# MiniSystem_Ports.net
KiCad netlist of a schematic drawn in Altium Designer
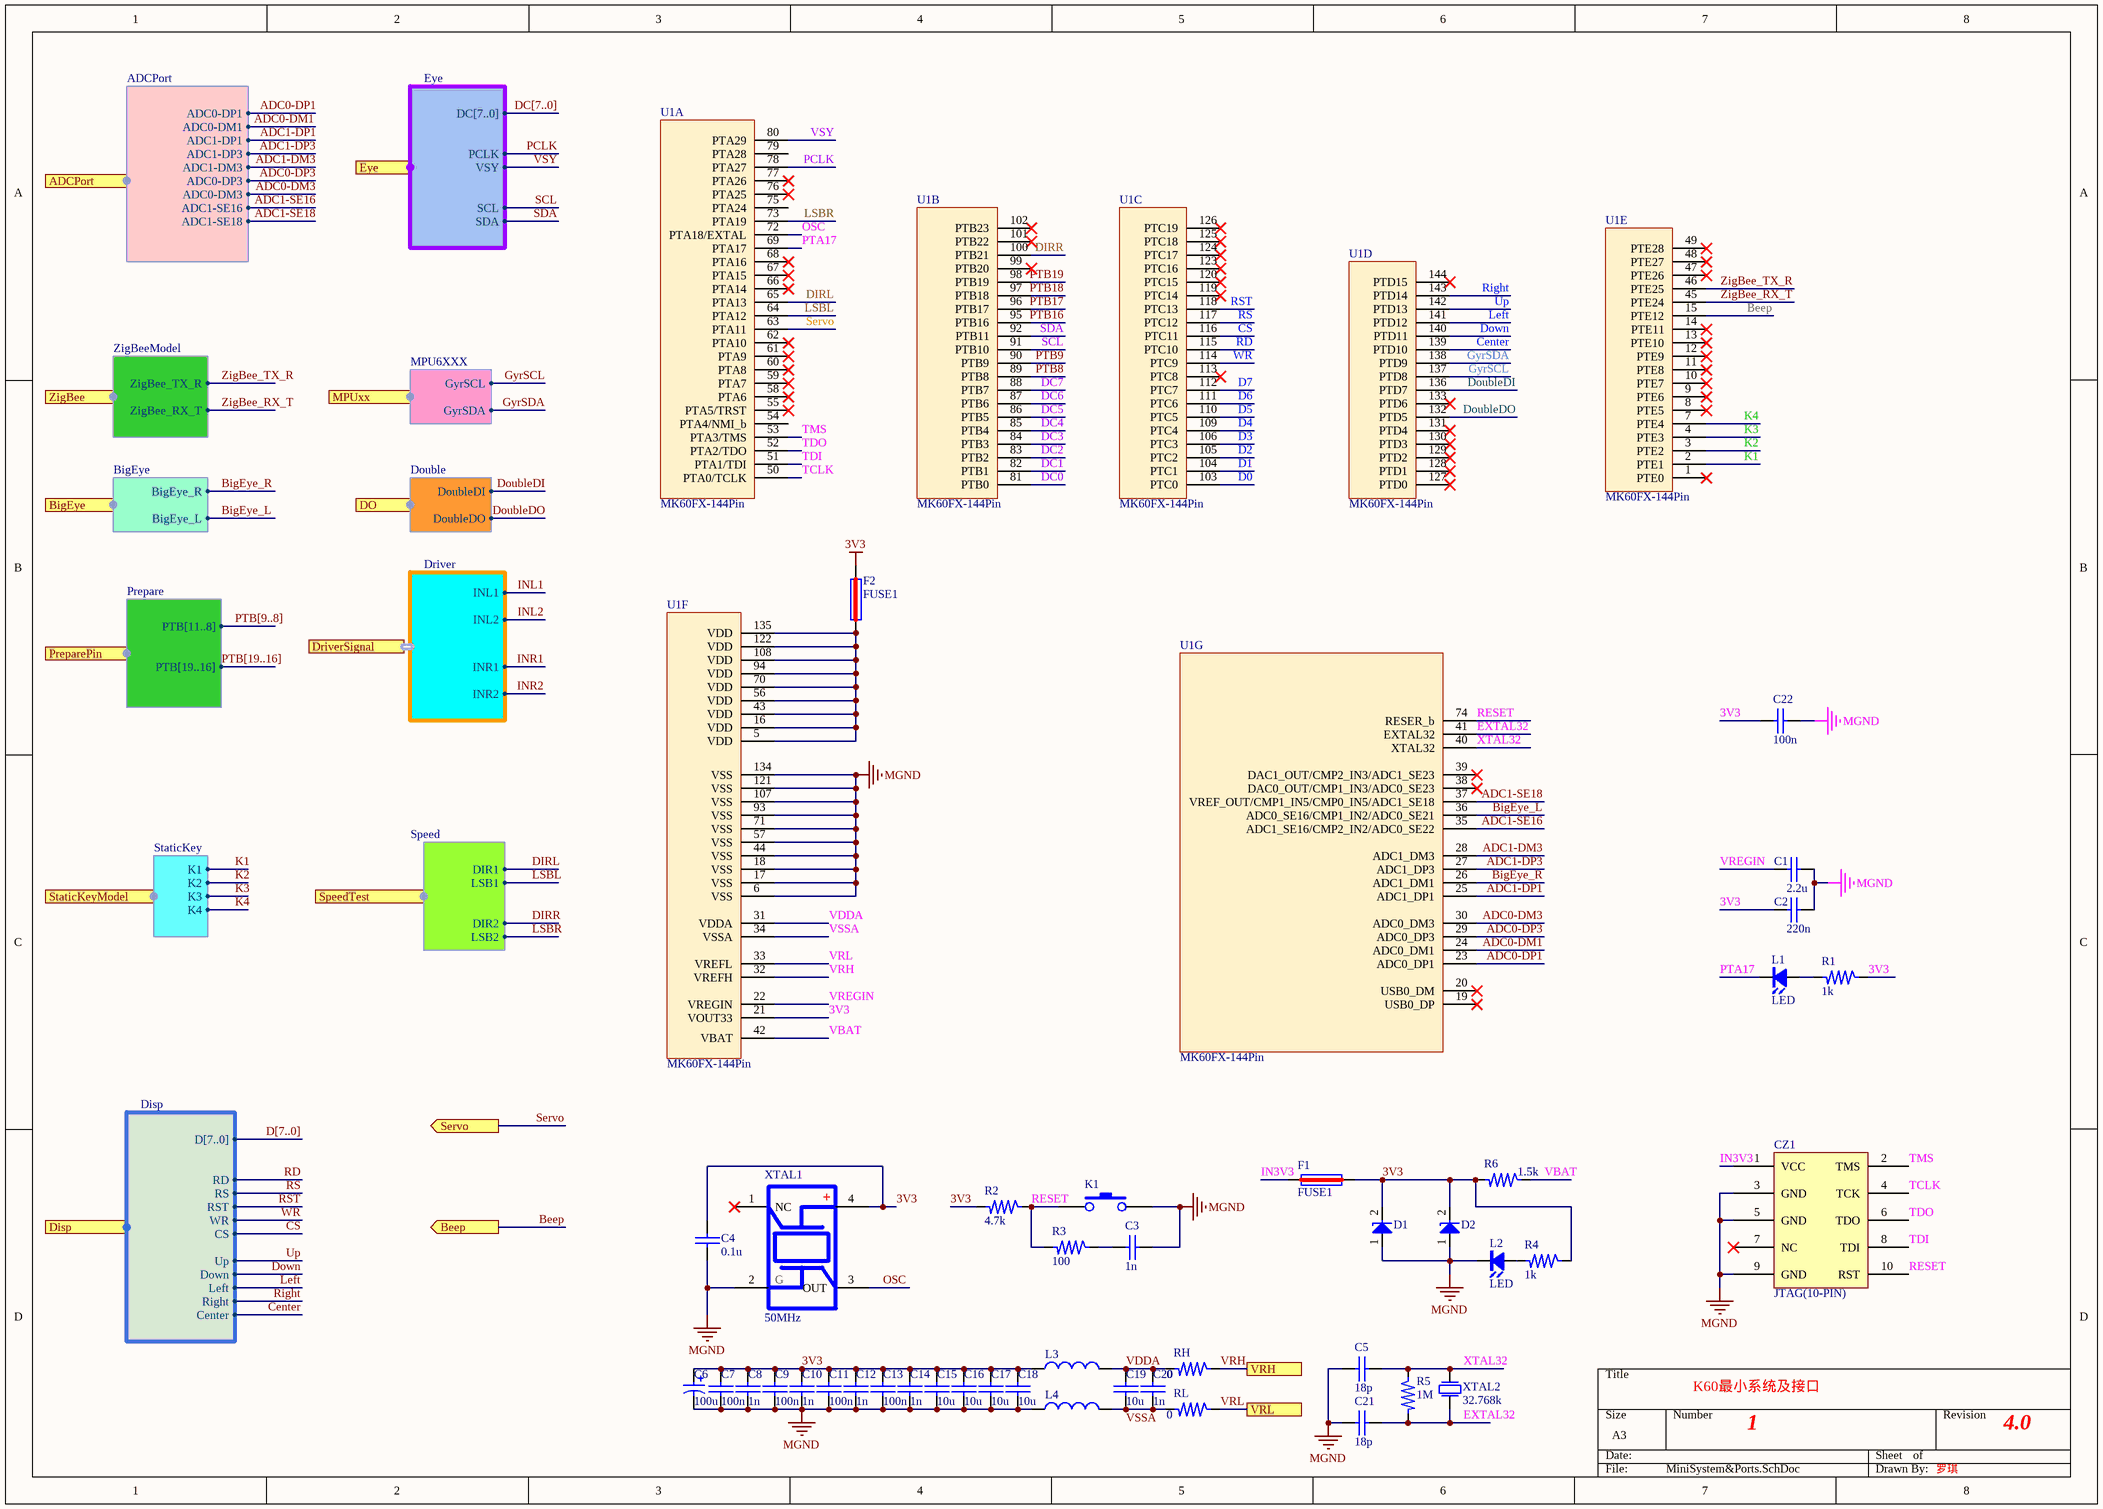
[diagram p0: MiniSystem&Ports.SchDoc]

(export (version "E")
  (design (tool "Eeschema 10.0.6"))
  (components
    (comp (ref "C1")
      (value "2.2u")
      (footprint "C0603")
      (description "电容")
      (libsource (lib "LQ_Integrated_Library") (part "Capacitor"))
    )
    (comp (ref "C2")
      (value "220n")
      (footprint "C0603")
      (description "电容")
      (libsource (lib "LQ_Integrated_Library") (part "Capacitor"))
    )
    (comp (ref "C3")
      (value "1n")
      (footprint "C0603")
      (description "电容")
      (libsource (lib "LQ_Integrated_Library") (part "Capacitor"))
    )
    (comp (ref "C4")
      (value "0.1u")
      (footprint "C0603")
      (description "电容")
      (libsource (lib "LQ_Integrated_Library") (part "Capacitor"))
    )
    (comp (ref "C5")
      (value "18p")
      (footprint "C0603")
      (description "电容")
      (libsource (lib "LQ_Integrated_Library") (part "Capacitor"))
    )
    (comp (ref "C6")
      (value "100u")
      (footprint "CAP-E SMD-C")
      (description "极性电容")
      (libsource (lib "LQ_Integrated_Library") (part "Capacitor-Polarity"))
    )
    (comp (ref "C7")
      (value "100n")
      (footprint "C0603")
      (description "电容")
      (libsource (lib "LQ_Integrated_Library") (part "Capacitor"))
    )
    (comp (ref "C8")
      (value "1n")
      (footprint "C0603")
      (description "电容")
      (libsource (lib "LQ_Integrated_Library") (part "Capacitor"))
    )
    (comp (ref "C9")
      (value "100n")
      (footprint "C0603")
      (description "电容")
      (libsource (lib "LQ_Integrated_Library") (part "Capacitor"))
    )
    (comp (ref "C10")
      (value "1n")
      (footprint "C0603")
      (description "电容")
      (libsource (lib "LQ_Integrated_Library") (part "Capacitor"))
    )
    (comp (ref "C11")
      (value "100n")
      (footprint "C0603")
      (description "电容")
      (libsource (lib "LQ_Integrated_Library") (part "Capacitor"))
    )
    (comp (ref "C12")
      (value "1n")
      (footprint "C0603")
      (description "电容")
      (libsource (lib "LQ_Integrated_Library") (part "Capacitor"))
    )
    (comp (ref "C13")
      (value "100n")
      (footprint "C0603")
      (description "电容")
      (libsource (lib "LQ_Integrated_Library") (part "Capacitor"))
    )
    (comp (ref "C14")
      (value "1n")
      (footprint "C0603")
      (description "电容")
      (libsource (lib "LQ_Integrated_Library") (part "Capacitor"))
    )
    (comp (ref "C15")
      (value "10u")
      (footprint "C0805")
      (description "电容")
      (libsource (lib "LQ_Integrated_Library") (part "Capacitor"))
    )
    (comp (ref "C16")
      (value "10u")
      (footprint "C0805")
      (description "电容")
      (libsource (lib "LQ_Integrated_Library") (part "Capacitor"))
    )
    (comp (ref "C17")
      (value "10u")
      (footprint "C0805")
      (description "电容")
      (libsource (lib "LQ_Integrated_Library") (part "Capacitor"))
    )
    (comp (ref "C18")
      (value "10u")
      (footprint "C0805")
      (description "电容")
      (libsource (lib "LQ_Integrated_Library") (part "Capacitor"))
    )
    (comp (ref "C19")
      (value "10u")
      (footprint "C0805")
      (description "电容")
      (libsource (lib "LQ_Integrated_Library") (part "Capacitor"))
    )
    (comp (ref "C20")
      (value "1n")
      (footprint "C0603")
      (description "电容")
      (libsource (lib "LQ_Integrated_Library") (part "Capacitor"))
    )
    (comp (ref "C21")
      (value "18p")
      (footprint "C0603")
      (description "电容")
      (libsource (lib "LQ_Integrated_Library") (part "Capacitor"))
    )
    (comp (ref "C22")
      (value "100n")
      (footprint "C0603")
      (description "电容")
      (libsource (lib "LQ_Integrated_Library") (part "Capacitor"))
    )
    (comp (ref "CZ1")
      (value "JTAG(10-PIN)")
      (footprint "JTAG 10-pin Header")
      (libsource (lib "LQ_Integrated_Library") (part "JTAG(10-PIN)"))
    )
    (comp (ref "D1")
      (value "EN5819")
      (footprint "D1206")
      (libsource (lib "LQ_Integrated_Library") (part "DIODE稳压"))
    )
    (comp (ref "D2")
      (value "EN5819")
      (footprint "D1206")
      (libsource (lib "LQ_Integrated_Library") (part "DIODE稳压"))
    )
    (comp (ref "F1")
      (value "FUSE1")
      (footprint "FUSE-F1210")
      (description "FUSE")
      (libsource (lib "LQ_Integrated_Library") (part "FUSE1"))
    )
    (comp (ref "F2")
      (value "FUSE1")
      (footprint "FUSE-F1210")
      (description "FUSE")
      (libsource (lib "LQ_Integrated_Library") (part "FUSE1"))
    )
    (comp (ref "K1")
      (value "SW")
      (footprint "KEY-K2")
      (description "按键")
      (libsource (lib "LQ_Integrated_Library") (part "KEY"))
    )
    (comp (ref "L1")
      (value "LED")
      (footprint "LED0805TB")
      (libsource (lib "LQ_Integrated_Library") (part "LED"))
    )
    (comp (ref "L2")
      (value "LED")
      (footprint "LED0805TB")
      (libsource (lib "LQ_Integrated_Library") (part "LED"))
    )
    (comp (ref "L3")
      (value "INDUCTOR")
      (footprint "L0805")
      (description "Inductor")
      (libsource (lib "LQ_Integrated_Library") (part "INDUCTOR"))
    )
    (comp (ref "L4")
      (value "INDUCTOR")
      (footprint "L0805")
      (description "Inductor")
      (libsource (lib "LQ_Integrated_Library") (part "INDUCTOR"))
    )
    (comp (ref "R1")
      (value "1k")
      (footprint "R0603")
      (description "电阻")
      (libsource (lib "LQ_Integrated_Library") (part "Resistor"))
    )
    (comp (ref "R2")
      (value "4.7k")
      (footprint "R0603")
      (description "电阻")
      (libsource (lib "LQ_Integrated_Library") (part "Resistor"))
    )
    (comp (ref "R3")
      (value "100")
      (footprint "R0603")
      (description "电阻")
      (libsource (lib "LQ_Integrated_Library") (part "Resistor"))
    )
    (comp (ref "R4")
      (value "1k")
      (footprint "R0603")
      (description "电阻")
      (libsource (lib "LQ_Integrated_Library") (part "Resistor"))
    )
    (comp (ref "R5")
      (value "1M")
      (footprint "R0603")
      (description "电阻")
      (libsource (lib "LQ_Integrated_Library") (part "Resistor"))
    )
    (comp (ref "R6")
      (value "1.5k")
      (footprint "R0603")
      (description "电阻")
      (libsource (lib "LQ_Integrated_Library") (part "Resistor"))
    )
    (comp (ref "RH")
      (value "0")
      (footprint "R0603")
      (description "电阻")
      (libsource (lib "LQ_Integrated_Library") (part "Resistor"))
    )
    (comp (ref "RL")
      (value "0")
      (footprint "R0603")
      (description "电阻")
      (libsource (lib "LQ_Integrated_Library") (part "Resistor"))
    )
    (comp (ref "U1") (value "MK60FX-144Pin") (footprint "LQFP144") (libsource (lib "") (part "MK60FX144_1")))
    (comp (ref "XTAL1")
      (value "50MHz")
      (footprint "XTAL-6035")
      (libsource (lib "LQ_Integrated_Library") (part "XTAL-Active"))
    )
    (comp (ref "XTAL2")
      (value "32.768k")
      (footprint "XTAL_32.768")
      (description "CRYSTAL")
      (libsource (lib "LQ_Integrated_Library") (part "XTAL"))
    )
  )
  (nets
    (net (code "12") (name "/ADC0-DM1") (class "Default")
      (node (ref "U1") (pin "24") (pinfunction "ADC0_DM1_24") (pintype "passive"))
    )
    (net (code "13") (name "/ADC0-DM3") (class "Default")
      (node (ref "U1") (pin "30") (pinfunction "ADC0_DM3_30") (pintype "passive"))
    )
    (net (code "14") (name "/ADC0-DP1") (class "Default")
      (node (ref "U1") (pin "23") (pinfunction "ADC0_DP1_23") (pintype "passive"))
    )
    (net (code "15") (name "/ADC0-DP3") (class "Default")
      (node (ref "U1") (pin "29") (pinfunction "ADC0_DP3_29") (pintype "passive"))
    )
    (net (code "16") (name "/ADC1-DM3") (class "Default")
      (node (ref "U1") (pin "28") (pinfunction "ADC1_DM3_28") (pintype "passive"))
    )
    (net (code "17") (name "/ADC1-DP1") (class "Default")
      (node (ref "U1") (pin "25") (pinfunction "ADC1_DP1_25") (pintype "passive"))
    )
    (net (code "18") (name "/ADC1-DP3") (class "Default")
      (node (ref "U1") (pin "27") (pinfunction "ADC1_DP3_27") (pintype "passive"))
    )
    (net (code "19") (name "/ADC1-SE16") (class "Default")
      (node (ref "U1") (pin "35") (pinfunction "ADC1_SE16/CMP2_IN2/ADC0_SE22_35") (pintype "passive"))
    )
    (net (code "20") (name "/ADC1-SE18") (class "Default")
      (node (ref "U1") (pin "37") (pinfunction "VREF_OUT/CMP1_IN5/CMP0_IN5/ADC1_SE18_37") (pintype "passive"))
    )
    (net (code "21") (name "/Beep") (class "Default")
      (node (ref "U1") (pin "15") (pinfunction "PTE12_15") (pintype "passive"))
    )
    (net (code "22") (name "/BigEye_L") (class "Default")
      (node (ref "U1") (pin "36") (pinfunction "ADC0_SE16/CMP1_IN2/ADC0_SE21_36") (pintype "passive"))
    )
    (net (code "23") (name "/BigEye_R") (class "Default")
      (node (ref "U1") (pin "26") (pinfunction "ADC1_DM1_26") (pintype "passive"))
    )
    (net (code "24") (name "/CS") (class "Default")
      (node (ref "U1") (pin "116") (pinfunction "PTC11_116") (pintype "passive"))
    )
    (net (code "25") (name "/Center") (class "Default")
      (node (ref "U1") (pin "139") (pinfunction "PTD10_139") (pintype "passive"))
    )
    (net (code "26") (name "/D0") (class "Default")
      (node (ref "U1") (pin "103") (pinfunction "PTC0_103") (pintype "passive"))
    )
    (net (code "27") (name "/D1") (class "Default")
      (node (ref "U1") (pin "104") (pinfunction "PTC1_104") (pintype "passive"))
    )
    (net (code "28") (name "/D2") (class "Default")
      (node (ref "U1") (pin "105") (pinfunction "PTC2_105") (pintype "passive"))
    )
    (net (code "29") (name "/D3") (class "Default")
      (node (ref "U1") (pin "106") (pinfunction "PTC3_106") (pintype "passive"))
    )
    (net (code "30") (name "/D4") (class "Default")
      (node (ref "U1") (pin "109") (pinfunction "PTC4_109") (pintype "passive"))
    )
    (net (code "31") (name "/D5") (class "Default")
      (node (ref "U1") (pin "110") (pinfunction "PTC5_110") (pintype "passive"))
    )
    (net (code "32") (name "/D6") (class "Default")
      (node (ref "U1") (pin "111") (pinfunction "PTC6_111") (pintype "passive"))
    )
    (net (code "33") (name "/D7") (class "Default")
      (node (ref "U1") (pin "112") (pinfunction "PTC7_112") (pintype "passive"))
    )
    (net (code "34") (name "/DC0") (class "Default")
      (node (ref "U1") (pin "81") (pinfunction "PTB0_81") (pintype "passive"))
    )
    (net (code "35") (name "/DC1") (class "Default")
      (node (ref "U1") (pin "82") (pinfunction "PTB1_82") (pintype "passive"))
    )
    (net (code "36") (name "/DC2") (class "Default")
      (node (ref "U1") (pin "83") (pinfunction "PTB2_83") (pintype "passive"))
    )
    (net (code "37") (name "/DC3") (class "Default")
      (node (ref "U1") (pin "84") (pinfunction "PTB3_84") (pintype "passive"))
    )
    (net (code "38") (name "/DC4") (class "Default")
      (node (ref "U1") (pin "85") (pinfunction "PTB4_85") (pintype "passive"))
    )
    (net (code "39") (name "/DC5") (class "Default")
      (node (ref "U1") (pin "86") (pinfunction "PTB5_86") (pintype "passive"))
    )
    (net (code "40") (name "/DC6") (class "Default")
      (node (ref "U1") (pin "87") (pinfunction "PTB6_87") (pintype "passive"))
    )
    (net (code "41") (name "/DC7") (class "Default")
      (node (ref "U1") (pin "88") (pinfunction "PTB7_88") (pintype "passive"))
    )
    (net (code "42") (name "/DIRL") (class "Default")
      (node (ref "U1") (pin "65") (pinfunction "PTA13_65") (pintype "passive"))
    )
    (net (code "43") (name "/DIRR") (class "Default")
      (node (ref "U1") (pin "100") (pinfunction "PTB21_100") (pintype "passive"))
    )
    (net (code "45") (name "/DoubleDI") (class "Default")
      (node (ref "U1") (pin "136") (pinfunction "PTD7_136") (pintype "passive"))
    )
    (net (code "46") (name "/DoubleDO") (class "Default")
      (node (ref "U1") (pin "132") (pinfunction "PTD5_132") (pintype "passive"))
    )
    (net (code "47") (name "/Down") (class "Default")
      (node (ref "U1") (pin "140") (pinfunction "PTD11_140") (pintype "passive"))
    )
    (net (code "48") (name "/EXTAL32") (class "Default")
      (node (ref "C21") (pin "2") (pinfunction "2_2") (pintype "passive"))
      (node (ref "R5") (pin "1") (pinfunction "1_1") (pintype "passive"))
      (node (ref "U1") (pin "41") (pinfunction "EXTAL32_41") (pintype "passive"))
      (node (ref "XTAL2") (pin "2") (pinfunction "P2_2") (pintype "passive"))
    )
    (net (code "50") (name "/GyrSCL") (class "Default")
      (node (ref "U1") (pin "137") (pinfunction "PTD8_137") (pintype "passive"))
    )
    (net (code "51") (name "/GyrSDA") (class "Default")
      (node (ref "U1") (pin "138") (pinfunction "PTD9_138") (pintype "passive"))
    )
    (net (code "52") (name "/IN3V3") (class "Default")
      (node (ref "CZ1") (pin "1") (pinfunction "VCC_1") (pintype "passive"))
      (node (ref "F1") (pin "1") (pinfunction "1_1") (pintype "passive"))
    )
    (net (code "57") (name "/K1") (class "Default")
      (node (ref "U1") (pin "2") (pinfunction "PTE1_2") (pintype "passive"))
    )
    (net (code "58") (name "/K2") (class "Default")
      (node (ref "U1") (pin "3") (pinfunction "PTE2_3") (pintype "passive"))
    )
    (net (code "59") (name "/K3") (class "Default")
      (node (ref "U1") (pin "4") (pinfunction "PTE3_4") (pintype "passive"))
    )
    (net (code "60") (name "/K4") (class "Default")
      (node (ref "U1") (pin "7") (pinfunction "PTE4_7") (pintype "passive"))
    )
    (net (code "61") (name "/LSBL") (class "Default")
      (node (ref "U1") (pin "64") (pinfunction "PTA12_64") (pintype "passive"))
    )
    (net (code "62") (name "/LSBR") (class "Default")
      (node (ref "U1") (pin "73") (pinfunction "PTA19_73") (pintype "passive"))
    )
    (net (code "63") (name "/Left") (class "Default")
      (node (ref "U1") (pin "141") (pinfunction "PTD12_141") (pintype "passive"))
    )
    (net (code "64") (name "/OSC") (class "Default")
      (node (ref "U1") (pin "72") (pinfunction "PTA18/EXTAL_72") (pintype "passive"))
      (node (ref "XTAL1") (pin "3") (pinfunction "OUT_3") (pintype "passive"))
    )
    (net (code "65") (name "/PCLK") (class "Default")
      (node (ref "U1") (pin "78") (pinfunction "PTA27_78") (pintype "passive"))
    )
    (net (code "66") (name "/PTA17") (class "Default")
      (node (ref "L1") (pin "2") (pinfunction "K_2") (pintype "passive"))
      (node (ref "U1") (pin "69") (pinfunction "PTA17_69") (pintype "passive"))
    )
    (net (code "67") (name "/PTB8") (class "Default")
      (node (ref "U1") (pin "89") (pinfunction "PTB8_89") (pintype "passive"))
    )
    (net (code "68") (name "/PTB9") (class "Default")
      (node (ref "U1") (pin "90") (pinfunction "PTB9_90") (pintype "passive"))
    )
    (net (code "69") (name "/PTB16") (class "Default")
      (node (ref "U1") (pin "95") (pinfunction "PTB16_95") (pintype "passive"))
    )
    (net (code "70") (name "/PTB17") (class "Default")
      (node (ref "U1") (pin "96") (pinfunction "PTB17_96") (pintype "passive"))
    )
    (net (code "71") (name "/PTB18") (class "Default")
      (node (ref "U1") (pin "97") (pinfunction "PTB18_97") (pintype "passive"))
    )
    (net (code "72") (name "/PTB19") (class "Default")
      (node (ref "U1") (pin "98") (pinfunction "PTB19_98") (pintype "passive"))
    )
    (net (code "75") (name "/RD") (class "Default")
      (node (ref "U1") (pin "115") (pinfunction "PTC10_115") (pintype "passive"))
    )
    (net (code "76") (name "/RESET") (class "Default")
      (node (ref "CZ1") (pin "10") (pinfunction "RST_10") (pintype "passive"))
      (node (ref "K1") (pin "1") (pinfunction "1_1") (pintype "passive"))
      (node (ref "R2") (pin "2") (pinfunction "2_2") (pintype "passive"))
      (node (ref "R3") (pin "1") (pinfunction "1_1") (pintype "passive"))
      (node (ref "U1") (pin "74") (pinfunction "RESER_b_74") (pintype "passive"))
    )
    (net (code "77") (name "/RS") (class "Default")
      (node (ref "U1") (pin "117") (pinfunction "PTC12_117") (pintype "passive"))
    )
    (net (code "78") (name "/RST") (class "Default")
      (node (ref "U1") (pin "118") (pinfunction "PTC13_118") (pintype "passive"))
    )
    (net (code "79") (name "/Right") (class "Default")
      (node (ref "U1") (pin "143") (pinfunction "PTD14_143") (pintype "passive"))
    )
    (net (code "80") (name "/SCL") (class "Default")
      (node (ref "U1") (pin "91") (pinfunction "PTB10_91") (pintype "passive"))
    )
    (net (code "81") (name "/SDA") (class "Default")
      (node (ref "U1") (pin "92") (pinfunction "PTB11_92") (pintype "passive"))
    )
    (net (code "82") (name "/Servo") (class "Default")
      (node (ref "U1") (pin "63") (pinfunction "PTA11_63") (pintype "passive"))
    )
    (net (code "83") (name "/TCLK") (class "Default")
      (node (ref "CZ1") (pin "4") (pinfunction "TCK_4") (pintype "passive"))
      (node (ref "U1") (pin "50") (pinfunction "PTA0/TCLK_50") (pintype "passive"))
    )
    (net (code "84") (name "/TDI") (class "Default")
      (node (ref "CZ1") (pin "8") (pinfunction "TDI_8") (pintype "passive"))
      (node (ref "U1") (pin "51") (pinfunction "PTA1/TDI_51") (pintype "passive"))
    )
    (net (code "85") (name "/TDO") (class "Default")
      (node (ref "CZ1") (pin "6") (pinfunction "TDO_6") (pintype "passive"))
      (node (ref "U1") (pin "52") (pinfunction "PTA2/TDO_52") (pintype "passive"))
    )
    (net (code "86") (name "/TMS") (class "Default")
      (node (ref "CZ1") (pin "2") (pinfunction "TMS_2") (pintype "passive"))
      (node (ref "U1") (pin "53") (pinfunction "PTA3/TMS_53") (pintype "passive"))
    )
    (net (code "87") (name "/Up") (class "Default")
      (node (ref "U1") (pin "142") (pinfunction "PTD13_142") (pintype "passive"))
    )
    (net (code "88") (name "/VBAT") (class "Default")
      (node (ref "R6") (pin "2") (pinfunction "2_2") (pintype "passive"))
      (node (ref "U1") (pin "42") (pinfunction "VBAT_42") (pintype "passive"))
    )
    (net (code "89") (name "/VDDA") (class "Default")
      (node (ref "C19") (pin "2") (pinfunction "2_2") (pintype "passive"))
      (node (ref "C20") (pin "2") (pinfunction "2_2") (pintype "passive"))
      (node (ref "L3") (pin "2") (pinfunction "2_2") (pintype "passive"))
      (node (ref "RH") (pin "1") (pinfunction "1_1") (pintype "passive"))
      (node (ref "U1") (pin "31") (pinfunction "VDDA_31") (pintype "passive"))
    )
    (net (code "90") (name "/VREGIN") (class "Default")
      (node (ref "C1") (pin "2") (pinfunction "2_2") (pintype "passive"))
      (node (ref "U1") (pin "22") (pinfunction "VREGIN_22") (pintype "passive"))
    )
    (net (code "91") (name "/VRH") (class "Default")
      (node (ref "RH") (pin "2") (pinfunction "2_2") (pintype "passive"))
      (node (ref "U1") (pin "32") (pinfunction "VREFH_32") (pintype "passive"))
    )
    (net (code "92") (name "/VRL") (class "Default")
      (node (ref "RL") (pin "2") (pinfunction "2_2") (pintype "passive"))
      (node (ref "U1") (pin "33") (pinfunction "VREFL_33") (pintype "passive"))
    )
    (net (code "93") (name "/VSSA") (class "Default")
      (node (ref "C19") (pin "1") (pinfunction "1_1") (pintype "passive"))
      (node (ref "C20") (pin "1") (pinfunction "1_1") (pintype "passive"))
      (node (ref "L4") (pin "2") (pinfunction "2_2") (pintype "passive"))
      (node (ref "RL") (pin "1") (pinfunction "1_1") (pintype "passive"))
      (node (ref "U1") (pin "34") (pinfunction "VSSA_34") (pintype "passive"))
    )
    (net (code "94") (name "/VSY") (class "Default")
      (node (ref "U1") (pin "80") (pinfunction "PTA29_80") (pintype "passive"))
    )
    (net (code "95") (name "/WR") (class "Default")
      (node (ref "U1") (pin "114") (pinfunction "PTC9_114") (pintype "passive"))
    )
    (net (code "96") (name "/XTAL32") (class "Default")
      (node (ref "C5") (pin "2") (pinfunction "2_2") (pintype "passive"))
      (node (ref "R5") (pin "2") (pinfunction "2_2") (pintype "passive"))
      (node (ref "U1") (pin "40") (pinfunction "XTAL32_40") (pintype "passive"))
      (node (ref "XTAL2") (pin "1") (pinfunction "P1_1") (pintype "passive"))
    )
    (net (code "97") (name "/ZigBee_RX_T") (class "Default")
      (node (ref "U1") (pin "45") (pinfunction "PTE24_45") (pintype "passive"))
    )
    (net (code "98") (name "/ZigBee_TX_R") (class "Default")
      (node (ref "U1") (pin "46") (pinfunction "PTE25_46") (pintype "passive"))
    )
    (net (code "110") (name "3V3") (class "Default")
      (node (ref "C10") (pin "2") (pinfunction "2_2") (pintype "passive"))
      (node (ref "C11") (pin "2") (pinfunction "2_2") (pintype "passive"))
      (node (ref "C12") (pin "2") (pinfunction "2_2") (pintype "passive"))
      (node (ref "C13") (pin "2") (pinfunction "2_2") (pintype "passive"))
      (node (ref "C14") (pin "2") (pinfunction "2_2") (pintype "passive"))
      (node (ref "C15") (pin "2") (pinfunction "2_2") (pintype "passive"))
      (node (ref "C16") (pin "2") (pinfunction "2_2") (pintype "passive"))
      (node (ref "C17") (pin "2") (pinfunction "2_2") (pintype "passive"))
      (node (ref "C18") (pin "2") (pinfunction "2_2") (pintype "passive"))
      (node (ref "C2") (pin "2") (pinfunction "2_2") (pintype "passive"))
      (node (ref "C22") (pin "1") (pinfunction "1_1") (pintype "passive"))
      (node (ref "C4") (pin "1") (pinfunction "1_1") (pintype "passive"))
      (node (ref "C6") (pin "1") (pinfunction "1_1") (pintype "passive"))
      (node (ref "C7") (pin "2") (pinfunction "2_2") (pintype "passive"))
      (node (ref "C8") (pin "2") (pinfunction "2_2") (pintype "passive"))
      (node (ref "C9") (pin "2") (pinfunction "2_2") (pintype "passive"))
      (node (ref "D1") (pin "2") (pintype "passive"))
      (node (ref "D2") (pin "2") (pintype "passive"))
      (node (ref "F1") (pin "2") (pinfunction "2_2") (pintype "passive"))
      (node (ref "F2") (pin "2") (pinfunction "2_2") (pintype "passive"))
      (node (ref "L3") (pin "1") (pinfunction "1_1") (pintype "passive"))
      (node (ref "R1") (pin "2") (pinfunction "2_2") (pintype "passive"))
      (node (ref "R2") (pin "1") (pinfunction "1_1") (pintype "passive"))
      (node (ref "R4") (pin "2") (pinfunction "2_2") (pintype "passive"))
      (node (ref "R6") (pin "1") (pinfunction "1_1") (pintype "passive"))
      (node (ref "U1") (pin "21") (pinfunction "VOUT33_21") (pintype "passive"))
      (node (ref "XTAL1") (pin "4") (pinfunction "VCC_4") (pintype "passive"))
    )
    (net (code "111") (name "MGND") (class "Default")
      (node (ref "C1") (pin "1") (pinfunction "1_1") (pintype "passive"))
      (node (ref "C10") (pin "1") (pinfunction "1_1") (pintype "passive"))
      (node (ref "C11") (pin "1") (pinfunction "1_1") (pintype "passive"))
      (node (ref "C12") (pin "1") (pinfunction "1_1") (pintype "passive"))
      (node (ref "C13") (pin "1") (pinfunction "1_1") (pintype "passive"))
      (node (ref "C14") (pin "1") (pinfunction "1_1") (pintype "passive"))
      (node (ref "C15") (pin "1") (pinfunction "1_1") (pintype "passive"))
      (node (ref "C16") (pin "1") (pinfunction "1_1") (pintype "passive"))
      (node (ref "C17") (pin "1") (pinfunction "1_1") (pintype "passive"))
      (node (ref "C18") (pin "1") (pinfunction "1_1") (pintype "passive"))
      (node (ref "C2") (pin "1") (pinfunction "1_1") (pintype "passive"))
      (node (ref "C21") (pin "1") (pinfunction "1_1") (pintype "passive"))
      (node (ref "C22") (pin "2") (pinfunction "2_2") (pintype "passive"))
      (node (ref "C3") (pin "2") (pinfunction "2_2") (pintype "passive"))
      (node (ref "C4") (pin "2") (pinfunction "2_2") (pintype "passive"))
      (node (ref "C5") (pin "1") (pinfunction "1_1") (pintype "passive"))
      (node (ref "C6") (pin "2") (pinfunction "2_2") (pintype "passive"))
      (node (ref "C7") (pin "1") (pinfunction "1_1") (pintype "passive"))
      (node (ref "C8") (pin "1") (pinfunction "1_1") (pintype "passive"))
      (node (ref "C9") (pin "1") (pinfunction "1_1") (pintype "passive"))
      (node (ref "CZ1") (pin "3") (pinfunction "GND_3") (pintype "passive"))
      (node (ref "CZ1") (pin "5") (pinfunction "GND_5") (pintype "passive"))
      (node (ref "CZ1") (pin "9") (pinfunction "GND_9") (pintype "passive"))
      (node (ref "D1") (pin "1") (pintype "passive"))
      (node (ref "D2") (pin "1") (pintype "passive"))
      (node (ref "K1") (pin "2") (pinfunction "2_2") (pintype "passive"))
      (node (ref "L2") (pin "2") (pinfunction "K_2") (pintype "passive"))
      (node (ref "L4") (pin "1") (pinfunction "1_1") (pintype "passive"))
      (node (ref "U1") (pin "107") (pinfunction "VSS_107") (pintype "passive"))
      (node (ref "U1") (pin "121") (pinfunction "VSS_121") (pintype "passive"))
      (node (ref "U1") (pin "134") (pinfunction "VSS_134") (pintype "passive"))
      (node (ref "U1") (pin "17") (pinfunction "VSS_17") (pintype "passive"))
      (node (ref "U1") (pin "18") (pinfunction "VSS_18") (pintype "passive"))
      (node (ref "U1") (pin "44") (pinfunction "VSS_44") (pintype "passive"))
      (node (ref "U1") (pin "57") (pinfunction "VSS_57") (pintype "passive"))
      (node (ref "U1") (pin "6") (pinfunction "VSS_6") (pintype "passive"))
      (node (ref "U1") (pin "71") (pinfunction "VSS_71") (pintype "passive"))
      (node (ref "U1") (pin "93") (pinfunction "VSS_93") (pintype "passive"))
      (node (ref "XTAL1") (pin "2") (pinfunction "GND_2") (pintype "passive"))
    )
    (net (code "112") (name "Net-(C3-Pad1)") (class "Default")
      (node (ref "C3") (pin "1") (pinfunction "1_1") (pintype "passive"))
      (node (ref "R3") (pin "2") (pinfunction "2_2") (pintype "passive"))
    )
    (net (code "113") (name "Net-(F2-Pad1)") (class "Default")
      (node (ref "F2") (pin "1") (pinfunction "1_1") (pintype "passive"))
      (node (ref "U1") (pin "108") (pinfunction "VDD_108") (pintype "passive"))
      (node (ref "U1") (pin "122") (pinfunction "VDD_122") (pintype "passive"))
      (node (ref "U1") (pin "135") (pinfunction "VDD_135") (pintype "passive"))
      (node (ref "U1") (pin "16") (pinfunction "VDD_16") (pintype "passive"))
      (node (ref "U1") (pin "43") (pinfunction "VDD_43") (pintype "passive"))
      (node (ref "U1") (pin "5") (pinfunction "VDD_5") (pintype "passive"))
      (node (ref "U1") (pin "56") (pinfunction "VDD_56") (pintype "passive"))
      (node (ref "U1") (pin "70") (pinfunction "VDD_70") (pintype "passive"))
      (node (ref "U1") (pin "94") (pinfunction "VDD_94") (pintype "passive"))
    )
    (net (code "114") (name "Net-(L1-A)") (class "Default")
      (node (ref "L1") (pin "1") (pinfunction "A_1") (pintype "passive"))
      (node (ref "R1") (pin "1") (pinfunction "1_1") (pintype "passive"))
    )
    (net (code "115") (name "Net-(L2-A)") (class "Default")
      (node (ref "L2") (pin "1") (pinfunction "A_1") (pintype "passive"))
      (node (ref "R4") (pin "1") (pinfunction "1_1") (pintype "passive"))
    )
    (net (code "116") (name "unconnected-(CZ1-NC-Pad7)") (class "Default")
      (node (ref "CZ1") (pin "7") (pinfunction "NC_7") (pintype "passive+no_connect"))
    )
    (net (code "117") (name "unconnected-(U1A-PTA4{slash}NMI_b-Pad54)") (class "Default")
      (node (ref "U1") (pin "54") (pinfunction "PTA4/NMI_b_54") (pintype "passive"))
    )
    (net (code "118") (name "unconnected-(U1A-PTA5{slash}TRST-Pad55)") (class "Default")
      (node (ref "U1") (pin "55") (pinfunction "PTA5/TRST_55") (pintype "passive+no_connect"))
    )
    (net (code "119") (name "unconnected-(U1A-PTA6-Pad58)") (class "Default")
      (node (ref "U1") (pin "58") (pinfunction "PTA6_58") (pintype "passive+no_connect"))
    )
    (net (code "120") (name "unconnected-(U1A-PTA7-Pad59)") (class "Default")
      (node (ref "U1") (pin "59") (pinfunction "PTA7_59") (pintype "passive+no_connect"))
    )
    (net (code "121") (name "unconnected-(U1A-PTA8-Pad60)") (class "Default")
      (node (ref "U1") (pin "60") (pinfunction "PTA8_60") (pintype "passive+no_connect"))
    )
    (net (code "122") (name "unconnected-(U1A-PTA9-Pad61)") (class "Default")
      (node (ref "U1") (pin "61") (pinfunction "PTA9_61") (pintype "passive+no_connect"))
    )
    (net (code "123") (name "unconnected-(U1A-PTA10-Pad62)") (class "Default")
      (node (ref "U1") (pin "62") (pinfunction "PTA10_62") (pintype "passive+no_connect"))
    )
    (net (code "124") (name "unconnected-(U1A-PTA14-Pad66)") (class "Default")
      (node (ref "U1") (pin "66") (pinfunction "PTA14_66") (pintype "passive+no_connect"))
    )
    (net (code "125") (name "unconnected-(U1A-PTA15-Pad67)") (class "Default")
      (node (ref "U1") (pin "67") (pinfunction "PTA15_67") (pintype "passive+no_connect"))
    )
    (net (code "126") (name "unconnected-(U1A-PTA16-Pad68)") (class "Default")
      (node (ref "U1") (pin "68") (pinfunction "PTA16_68") (pintype "passive+no_connect"))
    )
    (net (code "127") (name "unconnected-(U1A-PTA24-Pad75)") (class "Default")
      (node (ref "U1") (pin "75") (pinfunction "PTA24_75") (pintype "passive"))
    )
    (net (code "128") (name "unconnected-(U1A-PTA25-Pad76)") (class "Default")
      (node (ref "U1") (pin "76") (pinfunction "PTA25_76") (pintype "passive+no_connect"))
    )
    (net (code "129") (name "unconnected-(U1A-PTA26-Pad77)") (class "Default")
      (node (ref "U1") (pin "77") (pinfunction "PTA26_77") (pintype "passive+no_connect"))
    )
    (net (code "130") (name "unconnected-(U1A-PTA28-Pad79)") (class "Default")
      (node (ref "U1") (pin "79") (pinfunction "PTA28_79") (pintype "passive"))
    )
    (net (code "131") (name "unconnected-(U1B-PTB20-Pad99)") (class "Default")
      (node (ref "U1") (pin "99") (pinfunction "PTB20_99") (pintype "passive+no_connect"))
    )
    (net (code "132") (name "unconnected-(U1B-PTB22-Pad101)") (class "Default")
      (node (ref "U1") (pin "101") (pinfunction "PTB22_101") (pintype "passive+no_connect"))
    )
    (net (code "133") (name "unconnected-(U1B-PTB23-Pad102)") (class "Default")
      (node (ref "U1") (pin "102") (pinfunction "PTB23_102") (pintype "passive+no_connect"))
    )
    (net (code "134") (name "unconnected-(U1C-PTC8-Pad113)") (class "Default")
      (node (ref "U1") (pin "113") (pinfunction "PTC8_113") (pintype "passive+no_connect"))
    )
    (net (code "135") (name "unconnected-(U1C-PTC14-Pad119)") (class "Default")
      (node (ref "U1") (pin "119") (pinfunction "PTC14_119") (pintype "passive+no_connect"))
    )
    (net (code "136") (name "unconnected-(U1C-PTC15-Pad120)") (class "Default")
      (node (ref "U1") (pin "120") (pinfunction "PTC15_120") (pintype "passive+no_connect"))
    )
    (net (code "137") (name "unconnected-(U1C-PTC16-Pad123)") (class "Default")
      (node (ref "U1") (pin "123") (pinfunction "PTC16_123") (pintype "passive+no_connect"))
    )
    (net (code "138") (name "unconnected-(U1C-PTC17-Pad124)") (class "Default")
      (node (ref "U1") (pin "124") (pinfunction "PTC17_124") (pintype "passive+no_connect"))
    )
    (net (code "139") (name "unconnected-(U1C-PTC18-Pad125)") (class "Default")
      (node (ref "U1") (pin "125") (pinfunction "PTC18_125") (pintype "passive+no_connect"))
    )
    (net (code "140") (name "unconnected-(U1C-PTC19-Pad126)") (class "Default")
      (node (ref "U1") (pin "126") (pinfunction "PTC19_126") (pintype "passive+no_connect"))
    )
    (net (code "141") (name "unconnected-(U1D-PTD0-Pad127)") (class "Default")
      (node (ref "U1") (pin "127") (pinfunction "PTD0_127") (pintype "passive+no_connect"))
    )
    (net (code "142") (name "unconnected-(U1D-PTD1-Pad128)") (class "Default")
      (node (ref "U1") (pin "128") (pinfunction "PTD1_128") (pintype "passive+no_connect"))
    )
    (net (code "143") (name "unconnected-(U1D-PTD2-Pad129)") (class "Default")
      (node (ref "U1") (pin "129") (pinfunction "PTD2_129") (pintype "passive+no_connect"))
    )
    (net (code "144") (name "unconnected-(U1D-PTD3-Pad130)") (class "Default")
      (node (ref "U1") (pin "130") (pinfunction "PTD3_130") (pintype "passive+no_connect"))
    )
    (net (code "145") (name "unconnected-(U1D-PTD4-Pad131)") (class "Default")
      (node (ref "U1") (pin "131") (pinfunction "PTD4_131") (pintype "passive+no_connect"))
    )
    (net (code "146") (name "unconnected-(U1D-PTD6-Pad133)") (class "Default")
      (node (ref "U1") (pin "133") (pinfunction "PTD6_133") (pintype "passive+no_connect"))
    )
    (net (code "147") (name "unconnected-(U1D-PTD15-Pad144)") (class "Default")
      (node (ref "U1") (pin "144") (pinfunction "PTD15_144") (pintype "passive+no_connect"))
    )
    (net (code "148") (name "unconnected-(U1E-PTE0-Pad1)") (class "Default")
      (node (ref "U1") (pin "1") (pinfunction "PTE0_1") (pintype "passive+no_connect"))
    )
    (net (code "149") (name "unconnected-(U1E-PTE5-Pad8)") (class "Default")
      (node (ref "U1") (pin "8") (pinfunction "PTE5_8") (pintype "passive+no_connect"))
    )
    (net (code "150") (name "unconnected-(U1E-PTE6-Pad9)") (class "Default")
      (node (ref "U1") (pin "9") (pinfunction "PTE6_9") (pintype "passive+no_connect"))
    )
    (net (code "151") (name "unconnected-(U1E-PTE7-Pad10)") (class "Default")
      (node (ref "U1") (pin "10") (pinfunction "PTE7_10") (pintype "passive+no_connect"))
    )
    (net (code "152") (name "unconnected-(U1E-PTE8-Pad11)") (class "Default")
      (node (ref "U1") (pin "11") (pinfunction "PTE8_11") (pintype "passive+no_connect"))
    )
    (net (code "153") (name "unconnected-(U1E-PTE9-Pad12)") (class "Default")
      (node (ref "U1") (pin "12") (pinfunction "PTE9_12") (pintype "passive+no_connect"))
    )
    (net (code "154") (name "unconnected-(U1E-PTE10-Pad13)") (class "Default")
      (node (ref "U1") (pin "13") (pinfunction "PTE10_13") (pintype "passive+no_connect"))
    )
    (net (code "155") (name "unconnected-(U1E-PTE11-Pad14)") (class "Default")
      (node (ref "U1") (pin "14") (pinfunction "PTE11_14") (pintype "passive+no_connect"))
    )
    (net (code "156") (name "unconnected-(U1E-PTE26-Pad47)") (class "Default")
      (node (ref "U1") (pin "47") (pinfunction "PTE26_47") (pintype "passive+no_connect"))
    )
    (net (code "157") (name "unconnected-(U1E-PTE27-Pad48)") (class "Default")
      (node (ref "U1") (pin "48") (pinfunction "PTE27_48") (pintype "passive+no_connect"))
    )
    (net (code "158") (name "unconnected-(U1E-PTE28-Pad49)") (class "Default")
      (node (ref "U1") (pin "49") (pinfunction "PTE28_49") (pintype "passive+no_connect"))
    )
    (net (code "159") (name "unconnected-(U1G-DAC0_OUT{slash}CMP1_IN3{slash}ADC0_SE23-Pad38)") (class "Default")
      (node (ref "U1") (pin "38") (pinfunction "DAC0_OUT/CMP1_IN3/ADC0_SE23_38") (pintype "passive+no_connect"))
    )
    (net (code "160") (name "unconnected-(U1G-DAC1_OUT{slash}CMP2_IN3{slash}ADC1_SE23-Pad39)") (class "Default")
      (node (ref "U1") (pin "39") (pinfunction "DAC1_OUT/CMP2_IN3/ADC1_SE23_39") (pintype "passive+no_connect"))
    )
    (net (code "161") (name "unconnected-(U1G-USB0_DM-Pad20)") (class "Default")
      (node (ref "U1") (pin "20") (pinfunction "USB0_DM_20") (pintype "passive+no_connect"))
    )
    (net (code "162") (name "unconnected-(U1G-USB0_DP-Pad19)") (class "Default")
      (node (ref "U1") (pin "19") (pinfunction "USB0_DP_19") (pintype "passive+no_connect"))
    )
    (net (code "163") (name "unconnected-(XTAL1-NC-Pad1)") (class "Default")
      (node (ref "XTAL1") (pin "1") (pinfunction "NC_1") (pintype "passive+no_connect"))
    )
  )
)
